# T08-Schematic.net
KiCad netlist of a schematic drawn in EAGLE
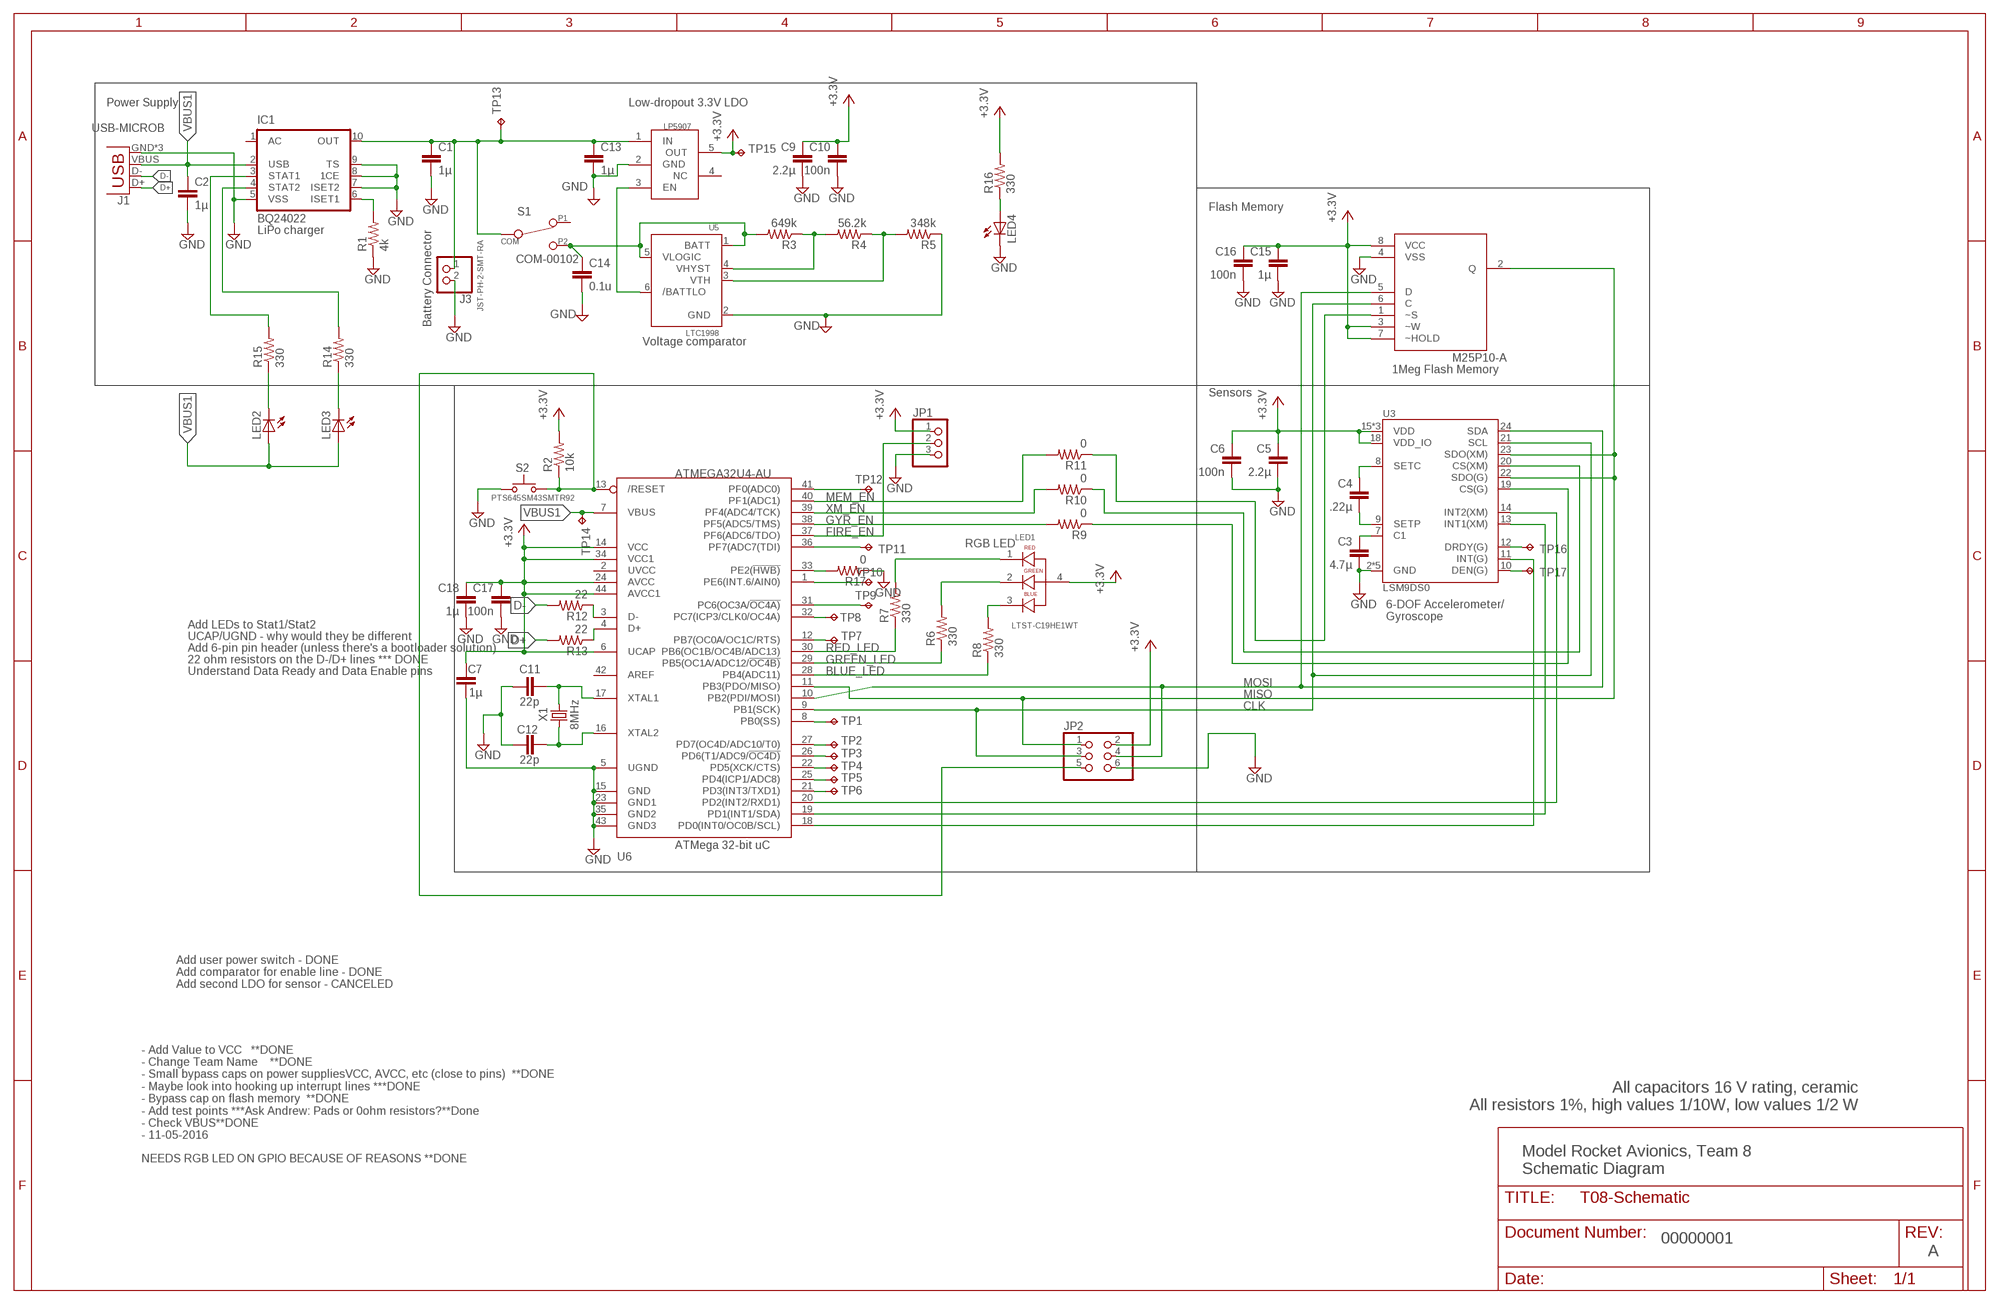
[diagram p0: schematic, sheet 1]

(export (version "E")
  (design (tool "Eeschema 10.0.6"))
  (components
    (comp (ref "C1")
      (value "1µ")
      (footprint "eagle-import:C0603")
      (libsource (lib "eagle-import") (part "C-EUC0603"))
    )
    (comp (ref "C2")
      (value "1µ")
      (footprint "eagle-import:C0805")
      (libsource (lib "eagle-import") (part "C-EUC0805"))
    )
    (comp (ref "C3")
      (value "4.7µ")
      (footprint "eagle-import:C0603")
      (libsource (lib "eagle-import") (part "C-EUC0603"))
    )
    (comp (ref "C4")
      (value ".22µ")
      (footprint "eagle-import:C0603")
      (libsource (lib "eagle-import") (part "C-EUC0603"))
    )
    (comp (ref "C5")
      (value "2.2µ")
      (footprint "eagle-import:C0603")
      (libsource (lib "eagle-import") (part "C-EUC0603"))
    )
    (comp (ref "C6")
      (value "100n")
      (footprint "eagle-import:C0603")
      (libsource (lib "eagle-import") (part "C-EUC0603"))
    )
    (comp (ref "C7")
      (value "1µ")
      (footprint "eagle-import:C0603")
      (libsource (lib "eagle-import") (part "C-EUC0603"))
    )
    (comp (ref "C9")
      (value "2.2µ")
      (footprint "eagle-import:C0603")
      (libsource (lib "eagle-import") (part "C-EUC0603"))
    )
    (comp (ref "C10")
      (value "100n")
      (footprint "eagle-import:C0603")
      (libsource (lib "eagle-import") (part "C-EUC0603"))
    )
    (comp (ref "C11")
      (value "22p")
      (footprint "eagle-import:C0603")
      (libsource (lib "eagle-import") (part "C-EUC0603"))
    )
    (comp (ref "C12")
      (value "22p")
      (footprint "eagle-import:C0603")
      (libsource (lib "eagle-import") (part "C-EUC0603"))
    )
    (comp (ref "C13")
      (value "1µ")
      (footprint "eagle-import:C0603")
      (libsource (lib "eagle-import") (part "C-EUC0603"))
    )
    (comp (ref "C14")
      (value "0.1u")
      (footprint "eagle-import:C0603")
      (libsource (lib "eagle-import") (part "C-EUC0603"))
    )
    (comp (ref "C15")
      (value "1µ")
      (footprint "eagle-import:C0603")
      (libsource (lib "eagle-import") (part "C-EUC0603"))
    )
    (comp (ref "C16")
      (value "100n")
      (footprint "eagle-import:C0603")
      (libsource (lib "eagle-import") (part "C-EUC0603"))
    )
    (comp (ref "C17")
      (value "100n")
      (footprint "eagle-import:C0603")
      (libsource (lib "eagle-import") (part "C-EUC0603"))
    )
    (comp (ref "C18")
      (value "1µ")
      (footprint "eagle-import:C0603")
      (libsource (lib "eagle-import") (part "C-EUC0603"))
    )
    (comp (ref "IC1")
      (value "BQ24022")
      (footprint "eagle-import:DRC-S-PVSON-N10")
      (libsource (lib "eagle-import") (part "BQ24022"))
    )
    (comp (ref "J1")
      (value "USB-MICROB")
      (footprint "eagle-import:USB-MICROB")
      (libsource (lib "eagle-import") (part "USB-MICROB"))
    )
    (comp (ref "J3")
      (value "JST-PH-2-SMT-RA")
      (footprint "eagle-import:JST-PH-2-SMT-RA")
      (libsource (lib "eagle-import") (part "JST_2PIN-SMT-RA"))
    )
    (comp (ref "JP1")
      (value "PINHD-1X3")
      (footprint "eagle-import:1X03")
      (libsource (lib "eagle-import") (part "PINHD-1X3"))
    )
    (comp (ref "JP2")
      (value "PINHD-2X3")
      (footprint "eagle-import:2X03")
      (libsource (lib "eagle-import") (part "PINHD-2X3"))
    )
    (comp (ref "LED1")
      (value "LTST-C19HE1WT")
      (footprint "eagle-import:LEDSC85P160X160X35-4N")
      (fields (field (name "MF") "Lite-On") (field (name "PRICE") "0.59 USD"))
      (libsource (lib "eagle-import") (part "LTST-C19HE1WT"))
    )
    (comp (ref "LED2")
      (value "LEDCHIP-LED0603")
      (footprint "eagle-import:CHIP-LED0603")
      (libsource (lib "eagle-import") (part "LEDCHIP-LED0603"))
    )
    (comp (ref "LED3")
      (value "LEDCHIP-LED0603")
      (footprint "eagle-import:CHIP-LED0603")
      (libsource (lib "eagle-import") (part "LEDCHIP-LED0603"))
    )
    (comp (ref "LED4")
      (value "LEDCHIP-LED0603")
      (footprint "eagle-import:CHIP-LED0603")
      (libsource (lib "eagle-import") (part "LEDCHIP-LED0603"))
    )
    (comp (ref "R1")
      (value "4k")
      (footprint "eagle-import:R0603")
      (libsource (lib "eagle-import") (part "R-US_R0603"))
    )
    (comp (ref "R2")
      (value "10k")
      (footprint "eagle-import:R0805")
      (libsource (lib "eagle-import") (part "R-US_R0805"))
    )
    (comp (ref "R3")
      (value "649k")
      (footprint "eagle-import:R0603")
      (libsource (lib "eagle-import") (part "R-US_R0603"))
    )
    (comp (ref "R4")
      (value "56.2k")
      (footprint "eagle-import:R0603")
      (libsource (lib "eagle-import") (part "R-US_R0603"))
    )
    (comp (ref "R5")
      (value "348k")
      (footprint "eagle-import:R0603")
      (libsource (lib "eagle-import") (part "R-US_R0603"))
    )
    (comp (ref "R6")
      (value "330")
      (footprint "eagle-import:R0805")
      (libsource (lib "eagle-import") (part "R-US_R0805"))
    )
    (comp (ref "R7")
      (value "330")
      (footprint "eagle-import:R0805")
      (libsource (lib "eagle-import") (part "R-US_R0805"))
    )
    (comp (ref "R8")
      (value "330")
      (footprint "eagle-import:R0805")
      (libsource (lib "eagle-import") (part "R-US_R0805"))
    )
    (comp (ref "R9")
      (value "0")
      (footprint "eagle-import:R0603")
      (libsource (lib "eagle-import") (part "R-US_R0603"))
    )
    (comp (ref "R10")
      (value "0")
      (footprint "eagle-import:R0603")
      (libsource (lib "eagle-import") (part "R-US_R0603"))
    )
    (comp (ref "R11")
      (value "0")
      (footprint "eagle-import:R0603")
      (libsource (lib "eagle-import") (part "R-US_R0603"))
    )
    (comp (ref "R12")
      (value "22")
      (footprint "eagle-import:R0603")
      (libsource (lib "eagle-import") (part "R-US_R0603"))
    )
    (comp (ref "R13")
      (value "22")
      (footprint "eagle-import:R0603")
      (libsource (lib "eagle-import") (part "R-US_R0603"))
    )
    (comp (ref "R14")
      (value "330")
      (footprint "eagle-import:R0805")
      (libsource (lib "eagle-import") (part "R-US_R0805"))
    )
    (comp (ref "R15")
      (value "330")
      (footprint "eagle-import:R0805")
      (libsource (lib "eagle-import") (part "R-US_R0805"))
    )
    (comp (ref "R16")
      (value "330")
      (footprint "eagle-import:R0805")
      (libsource (lib "eagle-import") (part "R-US_R0805"))
    )
    (comp (ref "R17")
      (value "0")
      (footprint "eagle-import:R0603")
      (libsource (lib "eagle-import") (part "R-US_R0603"))
    )
    (comp (ref "S1")
      (value "COM-00102")
      (footprint "eagle-import:ESWITCH")
      (libsource (lib "eagle-import") (part "COM-00102"))
    )
    (comp (ref "S2")
      (value "PTS645SM43SMTR92")
      (footprint "eagle-import:PTS645-SMD")
      (fields (field (name "MPN") "PTS645SM43SMTR92 LFS"))
      (libsource (lib "eagle-import") (part "PTS645S???SMTR"))
    )
    (comp (ref "TP1")
      (value "TPTP08R")
      (footprint "eagle-import:TP08R")
      (libsource (lib "eagle-import") (part "TPTP08R"))
    )
    (comp (ref "TP2")
      (value "TPTP08R")
      (footprint "eagle-import:TP08R")
      (libsource (lib "eagle-import") (part "TPTP08R"))
    )
    (comp (ref "TP3")
      (value "TPTP08R")
      (footprint "eagle-import:TP08R")
      (libsource (lib "eagle-import") (part "TPTP08R"))
    )
    (comp (ref "TP4")
      (value "TPTP08R")
      (footprint "eagle-import:TP08R")
      (libsource (lib "eagle-import") (part "TPTP08R"))
    )
    (comp (ref "TP5")
      (value "TPTP08R")
      (footprint "eagle-import:TP08R")
      (libsource (lib "eagle-import") (part "TPTP08R"))
    )
    (comp (ref "TP6")
      (value "TPTP08R")
      (footprint "eagle-import:TP08R")
      (libsource (lib "eagle-import") (part "TPTP08R"))
    )
    (comp (ref "TP7")
      (value "TPTP08R")
      (footprint "eagle-import:TP08R")
      (libsource (lib "eagle-import") (part "TPTP08R"))
    )
    (comp (ref "TP8")
      (value "TPTP08R")
      (footprint "eagle-import:TP08R")
      (libsource (lib "eagle-import") (part "TPTP08R"))
    )
    (comp (ref "TP9")
      (value "TPTP08R")
      (footprint "eagle-import:TP08R")
      (libsource (lib "eagle-import") (part "TPTP08R"))
    )
    (comp (ref "TP10")
      (value "TPTP08R")
      (footprint "eagle-import:TP08R")
      (libsource (lib "eagle-import") (part "TPTP08R"))
    )
    (comp (ref "TP11")
      (value "TPTP08R")
      (footprint "eagle-import:TP08R")
      (libsource (lib "eagle-import") (part "TPTP08R"))
    )
    (comp (ref "TP12")
      (value "TPTP08R")
      (footprint "eagle-import:TP08R")
      (libsource (lib "eagle-import") (part "TPTP08R"))
    )
    (comp (ref "TP13")
      (value "TPTP08R")
      (footprint "eagle-import:TP08R")
      (libsource (lib "eagle-import") (part "TPTP08R"))
    )
    (comp (ref "TP14")
      (value "TPTP08R")
      (footprint "eagle-import:TP08R")
      (libsource (lib "eagle-import") (part "TPTP08R"))
    )
    (comp (ref "TP15")
      (value "TPTP08R")
      (footprint "eagle-import:TP08R")
      (libsource (lib "eagle-import") (part "TPTP08R"))
    )
    (comp (ref "TP16")
      (value "TPTP08R")
      (footprint "eagle-import:TP08R")
      (libsource (lib "eagle-import") (part "TPTP08R"))
    )
    (comp (ref "TP17")
      (value "TPTP08R")
      (footprint "eagle-import:TP08R")
      (libsource (lib "eagle-import") (part "TPTP08R"))
    )
    (comp (ref "U1")
      (value "LP5907")
      (footprint "eagle-import:SOT23-5L")
      (libsource (lib "eagle-import") (part "LP5907"))
    )
    (comp (ref "U2")
      (value "M25P10-AVMN6TP_TR")
      (footprint "eagle-import:SOIC127P600X175-8N")
      (libsource (lib "eagle-import") (part "M25P10-AVMN6TP_TR"))
    )
    (comp (ref "U3")
      (value "LSM9DS0")
      (footprint "eagle-import:LGA-24")
      (fields (field (name "MF") "STMicroelectronics"))
      (libsource (lib "eagle-import") (part "LSM9DS0"))
    )
    (comp (ref "U5")
      (value "LTC1998")
      (footprint "eagle-import:TSOT23-6")
      (libsource (lib "eagle-import") (part "LTC1998"))
    )
    (comp (ref "U6")
      (value "ATMEGA32U4-AU")
      (footprint "eagle-import:TQFP44")
      (libsource (lib "eagle-import") (part "ATMEGA32U4-AU"))
    )
    (comp (ref "X1")
      (value "8MHz")
      (footprint "eagle-import:HC49")
      (fields (field (name "MPN") "ATS080B"))
      (libsource (lib "eagle-import") (part "CRYSTALS-NOGND-HC49/4H"))
    )
  )
  (nets
    (net (code "1") (name "+3.3V") (class "Default")
      (node (ref "C10") (pin "1") (pinfunction "1_1") (pintype "passive"))
      (node (ref "C15") (pin "1") (pinfunction "1_1") (pintype "passive"))
      (node (ref "C16") (pin "1") (pinfunction "1_1") (pintype "passive"))
      (node (ref "C17") (pin "1") (pinfunction "1_1") (pintype "passive"))
      (node (ref "C18") (pin "1") (pinfunction "1_1") (pintype "passive"))
      (node (ref "C5") (pin "1") (pinfunction "1_1") (pintype "passive"))
      (node (ref "C6") (pin "1") (pinfunction "1_1") (pintype "passive"))
      (node (ref "C7") (pin "1") (pinfunction "1_1") (pintype "passive"))
      (node (ref "C9") (pin "1") (pinfunction "1_1") (pintype "passive"))
      (node (ref "JP1") (pin "1") (pinfunction "1_1") (pintype "passive"))
      (node (ref "JP2") (pin "2") (pinfunction "2_2") (pintype "passive"))
      (node (ref "LED1") (pin "4") (pinfunction "4_4") (pintype "passive"))
      (node (ref "R16") (pin "2") (pinfunction "2_2") (pintype "passive"))
      (node (ref "R2") (pin "2") (pinfunction "2_2") (pintype "passive"))
      (node (ref "TP15") (pin "TP") (pinfunction "TP_TP") (pintype "input"))
      (node (ref "U1") (pin "5") (pinfunction "OUT_5") (pintype "bidirectional"))
      (node (ref "U2") (pin "3") (pinfunction "~{W}_3") (pintype "bidirectional"))
      (node (ref "U2") (pin "7") (pinfunction "~{HOLD}_7") (pintype "bidirectional"))
      (node (ref "U2") (pin "8") (pinfunction "VCC_8") (pintype "bidirectional"))
      (node (ref "U3") (pin "15") (pinfunction "VDD_15") (pintype "bidirectional"))
      (node (ref "U3") (pin "16") (pinfunction "VDD_16") (pintype "bidirectional"))
      (node (ref "U3") (pin "17") (pinfunction "VDD_17") (pintype "bidirectional"))
      (node (ref "U3") (pin "18") (pinfunction "VDD_IO_18") (pintype "bidirectional"))
      (node (ref "U6") (pin "14") (pinfunction "VCC_14") (pintype "bidirectional"))
      (node (ref "U6") (pin "24") (pinfunction "AVCC_24") (pintype "bidirectional"))
      (node (ref "U6") (pin "34") (pinfunction "VCC1_34") (pintype "bidirectional"))
      (node (ref "U6") (pin "44") (pinfunction "AVCC1_44") (pintype "bidirectional"))
      (node (ref "U6") (pin "6") (pinfunction "UCAP_6") (pintype "bidirectional"))
    )
    (net (code "2") (name "/BLUE_LED") (class "Default")
      (node (ref "R8") (pin "1") (pinfunction "1_1") (pintype "passive"))
      (node (ref "U6") (pin "28") (pinfunction "PB4(ADC11)_28") (pintype "bidirectional"))
    )
    (net (code "3") (name "/CLK") (class "Default")
      (node (ref "JP2") (pin "3") (pinfunction "3_3") (pintype "passive"))
      (node (ref "U2") (pin "6") (pinfunction "C_6") (pintype "bidirectional"))
      (node (ref "U3") (pin "21") (pinfunction "SCL_21") (pintype "bidirectional"))
      (node (ref "U6") (pin "9") (pinfunction "PB1(SCK)_9") (pintype "bidirectional"))
    )
    (net (code "4") (name "/FIRE_EN") (class "Default")
      (node (ref "JP1") (pin "2") (pinfunction "2_2") (pintype "passive"))
      (node (ref "U6") (pin "37") (pinfunction "PF6(ADC6/TDO)_37") (pintype "bidirectional"))
    )
    (net (code "5") (name "/GREEN_LED") (class "Default")
      (node (ref "R6") (pin "1") (pinfunction "1_1") (pintype "passive"))
      (node (ref "U6") (pin "29") (pinfunction "PB5(OC1A/ADC12/~{OC4B})_29") (pintype "bidirectional"))
    )
    (net (code "6") (name "/GYR_EN") (class "Default")
      (node (ref "R9") (pin "1") (pinfunction "1_1") (pintype "passive"))
      (node (ref "U3") (pin "19") (pinfunction "CS(G)_19") (pintype "bidirectional"))
    )
    (net (code "7") (name "/MEM_EN") (class "Default")
      (node (ref "R11") (pin "1") (pinfunction "1_1") (pintype "passive"))
      (node (ref "U2") (pin "1") (pinfunction "~{S}_1") (pintype "bidirectional"))
    )
    (net (code "8") (name "/MISO") (class "Default")
      (node (ref "JP2") (pin "1") (pinfunction "1_1") (pintype "passive"))
      (node (ref "U2") (pin "2") (pinfunction "Q_2") (pintype "bidirectional"))
      (node (ref "U3") (pin "22") (pinfunction "SDO(G)_22") (pintype "bidirectional"))
      (node (ref "U3") (pin "23") (pinfunction "SDO(XM)_23") (pintype "bidirectional"))
      (node (ref "U6") (pin "11") (pinfunction "PB3(PDO/MISO)_11") (pintype "bidirectional"))
    )
    (net (code "9") (name "/MOSI") (class "Default")
      (node (ref "JP2") (pin "4") (pinfunction "4_4") (pintype "passive"))
      (node (ref "U2") (pin "5") (pinfunction "D_5") (pintype "bidirectional"))
      (node (ref "U3") (pin "24") (pinfunction "SDA_24") (pintype "bidirectional"))
      (node (ref "U6") (pin "10") (pinfunction "PB2(PDI/MOSI)_10") (pintype "bidirectional"))
    )
    (net (code "10") (name "/RED_LED") (class "Default")
      (node (ref "R7") (pin "1") (pinfunction "1_1") (pintype "passive"))
      (node (ref "U6") (pin "30") (pinfunction "PB6(OC1B/OC4B/ADC13)_30") (pintype "bidirectional"))
    )
    (net (code "11") (name "/XM_EN") (class "Default")
      (node (ref "R10") (pin "1") (pinfunction "1_1") (pintype "passive"))
      (node (ref "U3") (pin "20") (pinfunction "CS(XM)_20") (pintype "bidirectional"))
    )
    (net (code "12") (name "D+") (class "Default")
      (node (ref "J1") (pin "D+") (pinfunction "D+_D+") (pintype "bidirectional"))
      (node (ref "R13") (pin "2") (pinfunction "2_2") (pintype "passive"))
    )
    (net (code "13") (name "D-") (class "Default")
      (node (ref "J1") (pin "D-") (pinfunction "D-_D-") (pintype "bidirectional"))
      (node (ref "R12") (pin "2") (pinfunction "2_2") (pintype "passive"))
    )
    (net (code "14") (name "GND") (class "Default")
      (node (ref "C1") (pin "2") (pinfunction "2_2") (pintype "passive"))
      (node (ref "C10") (pin "2") (pinfunction "2_2") (pintype "passive"))
      (node (ref "C11") (pin "2") (pinfunction "2_2") (pintype "passive"))
      (node (ref "C12") (pin "2") (pinfunction "2_2") (pintype "passive"))
      (node (ref "C13") (pin "2") (pinfunction "2_2") (pintype "passive"))
      (node (ref "C14") (pin "2") (pinfunction "2_2") (pintype "passive"))
      (node (ref "C15") (pin "2") (pinfunction "2_2") (pintype "passive"))
      (node (ref "C16") (pin "2") (pinfunction "2_2") (pintype "passive"))
      (node (ref "C17") (pin "2") (pinfunction "2_2") (pintype "passive"))
      (node (ref "C18") (pin "2") (pinfunction "2_2") (pintype "passive"))
      (node (ref "C2") (pin "2") (pinfunction "2_2") (pintype "passive"))
      (node (ref "C3") (pin "1") (pinfunction "1_1") (pintype "passive"))
      (node (ref "C5") (pin "2") (pinfunction "2_2") (pintype "passive"))
      (node (ref "C6") (pin "2") (pinfunction "2_2") (pintype "passive"))
      (node (ref "C7") (pin "2") (pinfunction "2_2") (pintype "passive"))
      (node (ref "C9") (pin "2") (pinfunction "2_2") (pintype "passive"))
      (node (ref "IC1") (pin "5") (pinfunction "VSS_5") (pintype "power_in"))
      (node (ref "IC1") (pin "7") (pinfunction "ISET2_7") (pintype "input"))
      (node (ref "IC1") (pin "8") (pinfunction "1CE_8") (pintype "input"))
      (node (ref "IC1") (pin "9") (pinfunction "TS_9") (pintype "input"))
      (node (ref "J1") (pin "GND") (pinfunction "GND_GND") (pintype "bidirectional"))
      (node (ref "J1") (pin "MT1") (pinfunction "GND_MT1") (pintype "bidirectional"))
      (node (ref "J1") (pin "MT2") (pinfunction "GND_MT2") (pintype "bidirectional"))
      (node (ref "J3") (pin "2") (pinfunction "1_2") (pintype "passive"))
      (node (ref "JP1") (pin "3") (pinfunction "3_3") (pintype "passive"))
      (node (ref "JP2") (pin "6") (pinfunction "6_6") (pintype "passive"))
      (node (ref "LED4") (pin "C") (pinfunction "C_C") (pintype "passive"))
      (node (ref "R1") (pin "1") (pinfunction "1_1") (pintype "passive"))
      (node (ref "R17") (pin "1") (pinfunction "1_1") (pintype "passive"))
      (node (ref "R5") (pin "1") (pinfunction "1_1") (pintype "passive"))
      (node (ref "S2") (pin "1") (pinfunction "P_1") (pintype "passive"))
      (node (ref "S2") (pin "2") (pinfunction "P_2") (pintype "passive"))
      (node (ref "U1") (pin "2") (pinfunction "GND_2") (pintype "bidirectional"))
      (node (ref "U2") (pin "4") (pinfunction "VSS_4") (pintype "bidirectional"))
      (node (ref "U3") (pin "2") (pinfunction "GND_2") (pintype "bidirectional"))
      (node (ref "U3") (pin "3") (pinfunction "GND_3") (pintype "bidirectional"))
      (node (ref "U3") (pin "4") (pinfunction "GND_4") (pintype "bidirectional"))
      (node (ref "U3") (pin "5") (pinfunction "GND_5") (pintype "bidirectional"))
      (node (ref "U3") (pin "6") (pinfunction "GND_6") (pintype "bidirectional"))
      (node (ref "U5") (pin "2") (pinfunction "GND_2") (pintype "bidirectional"))
      (node (ref "U6") (pin "15") (pinfunction "GND_15") (pintype "bidirectional"))
      (node (ref "U6") (pin "23") (pinfunction "GND1_23") (pintype "bidirectional"))
      (node (ref "U6") (pin "35") (pinfunction "GND2_35") (pintype "bidirectional"))
      (node (ref "U6") (pin "43") (pinfunction "GND3_43") (pintype "bidirectional"))
      (node (ref "U6") (pin "5") (pinfunction "UGND_5") (pintype "bidirectional"))
    )
    (net (code "15") (name "Net-(IC1A-ISET1)") (class "Default")
      (node (ref "IC1") (pin "6") (pinfunction "ISET1_6") (pintype "input"))
      (node (ref "R1") (pin "2") (pinfunction "2_2") (pintype "passive"))
    )
    (net (code "16") (name "Net-(IC1A-OUT)") (class "Default")
      (node (ref "C1") (pin "1") (pinfunction "1_1") (pintype "passive"))
      (node (ref "C13") (pin "1") (pinfunction "1_1") (pintype "passive"))
      (node (ref "IC1") (pin "10") (pinfunction "OUT_10") (pintype "output"))
      (node (ref "J3") (pin "1") (pinfunction "2_1") (pintype "passive"))
      (node (ref "S1") (pin "2") (pinfunction "COM_2") (pintype "bidirectional"))
      (node (ref "TP13") (pin "TP") (pinfunction "TP_TP") (pintype "input"))
      (node (ref "U1") (pin "1") (pinfunction "IN_1") (pintype "bidirectional"))
    )
    (net (code "17") (name "Net-(IC1A-STAT1)") (class "Default")
      (node (ref "IC1") (pin "3") (pinfunction "STAT1_3") (pintype "bidirectional"))
      (node (ref "R15") (pin "2") (pinfunction "2_2") (pintype "passive"))
    )
    (net (code "18") (name "Net-(IC1A-STAT2)") (class "Default")
      (node (ref "IC1") (pin "4") (pinfunction "STAT2_4") (pintype "bidirectional"))
      (node (ref "R14") (pin "2") (pinfunction "2_2") (pintype "passive"))
    )
    (net (code "19") (name "Net-(LED1-Pad1)") (class "Default")
      (node (ref "LED1") (pin "1") (pinfunction "1_1") (pintype "passive"))
      (node (ref "R7") (pin "2") (pinfunction "2_2") (pintype "passive"))
    )
    (net (code "20") (name "Net-(LED1-Pad2)") (class "Default")
      (node (ref "LED1") (pin "2") (pinfunction "2_2") (pintype "passive"))
      (node (ref "R6") (pin "2") (pinfunction "2_2") (pintype "passive"))
    )
    (net (code "21") (name "Net-(LED1-Pad3)") (class "Default")
      (node (ref "LED1") (pin "3") (pinfunction "3_3") (pintype "passive"))
      (node (ref "R8") (pin "2") (pinfunction "2_2") (pintype "passive"))
    )
    (net (code "22") (name "Net-(LED2-PadC)") (class "Default")
      (node (ref "LED2") (pin "C") (pinfunction "C_C") (pintype "passive"))
      (node (ref "R15") (pin "1") (pinfunction "1_1") (pintype "passive"))
    )
    (net (code "23") (name "Net-(LED3-PadC)") (class "Default")
      (node (ref "LED3") (pin "C") (pinfunction "C_C") (pintype "passive"))
      (node (ref "R14") (pin "1") (pinfunction "1_1") (pintype "passive"))
    )
    (net (code "24") (name "Net-(LED4-PadA)") (class "Default")
      (node (ref "LED4") (pin "A") (pinfunction "A_A") (pintype "passive"))
      (node (ref "R16") (pin "1") (pinfunction "1_1") (pintype "passive"))
    )
    (net (code "25") (name "Net-(S1-P2)") (class "Default")
      (node (ref "C14") (pin "1") (pinfunction "1_1") (pintype "passive"))
      (node (ref "R3") (pin "2") (pinfunction "2_2") (pintype "passive"))
      (node (ref "S1") (pin "3") (pinfunction "P2_3") (pintype "bidirectional"))
      (node (ref "U5") (pin "1") (pinfunction "BATT_1") (pintype "bidirectional"))
      (node (ref "U5") (pin "5") (pinfunction "VLOGIC_5") (pintype "bidirectional"))
    )
    (net (code "26") (name "Net-(U1-EN)") (class "Default")
      (node (ref "U1") (pin "3") (pinfunction "EN_3") (pintype "bidirectional"))
      (node (ref "U5") (pin "6") (pinfunction "/BATTLO_6") (pintype "bidirectional"))
    )
    (net (code "27") (name "Net-(U3-C1)") (class "Default")
      (node (ref "C3") (pin "2") (pinfunction "2_2") (pintype "passive"))
      (node (ref "U3") (pin "7") (pinfunction "C1_7") (pintype "bidirectional"))
    )
    (net (code "28") (name "Net-(U3-DEN(G))") (class "Default")
      (node (ref "TP17") (pin "TP") (pinfunction "TP_TP") (pintype "input"))
      (node (ref "U3") (pin "10") (pinfunction "DEN(G)_10") (pintype "bidirectional"))
    )
    (net (code "29") (name "Net-(U3-DRDY(G))") (class "Default")
      (node (ref "TP16") (pin "TP") (pinfunction "TP_TP") (pintype "input"))
      (node (ref "U3") (pin "12") (pinfunction "DRDY(G)_12") (pintype "bidirectional"))
    )
    (net (code "30") (name "Net-(U3-INT(G))") (class "Default")
      (node (ref "U3") (pin "11") (pinfunction "INT(G)_11") (pintype "bidirectional"))
      (node (ref "U6") (pin "18") (pinfunction "PD0(INT0/OC0B/SCL)_18") (pintype "bidirectional"))
    )
    (net (code "31") (name "Net-(U3-INT1(XM))") (class "Default")
      (node (ref "U3") (pin "13") (pinfunction "INT1(XM)_13") (pintype "bidirectional"))
      (node (ref "U6") (pin "19") (pinfunction "PD1(INT1/SDA)_19") (pintype "bidirectional"))
    )
    (net (code "32") (name "Net-(U3-INT2(XM))") (class "Default")
      (node (ref "U3") (pin "14") (pinfunction "INT2(XM)_14") (pintype "bidirectional"))
      (node (ref "U6") (pin "20") (pinfunction "PD2(INT2/RXD1)_20") (pintype "bidirectional"))
    )
    (net (code "33") (name "Net-(U3-SETC)") (class "Default")
      (node (ref "C4") (pin "2") (pinfunction "2_2") (pintype "passive"))
      (node (ref "U3") (pin "8") (pinfunction "SETC_8") (pintype "bidirectional"))
    )
    (net (code "34") (name "Net-(U3-SETP)") (class "Default")
      (node (ref "C4") (pin "1") (pinfunction "1_1") (pintype "passive"))
      (node (ref "U3") (pin "9") (pinfunction "SETP_9") (pintype "bidirectional"))
    )
    (net (code "35") (name "Net-(U5-VHYST)") (class "Default")
      (node (ref "R3") (pin "1") (pinfunction "1_1") (pintype "passive"))
      (node (ref "R4") (pin "2") (pinfunction "2_2") (pintype "passive"))
      (node (ref "U5") (pin "4") (pinfunction "VHYST_4") (pintype "bidirectional"))
    )
    (net (code "36") (name "Net-(U5-VTH)") (class "Default")
      (node (ref "R4") (pin "1") (pinfunction "1_1") (pintype "passive"))
      (node (ref "R5") (pin "2") (pinfunction "2_2") (pintype "passive"))
      (node (ref "U5") (pin "3") (pinfunction "VTH_3") (pintype "bidirectional"))
    )
    (net (code "37") (name "Net-(U6-D+)") (class "Default")
      (node (ref "R13") (pin "1") (pinfunction "1_1") (pintype "passive"))
      (node (ref "U6") (pin "4") (pinfunction "D+_4") (pintype "bidirectional"))
    )
    (net (code "38") (name "Net-(U6-D-)") (class "Default")
      (node (ref "R12") (pin "1") (pinfunction "1_1") (pintype "passive"))
      (node (ref "U6") (pin "3") (pinfunction "D-_3") (pintype "bidirectional"))
    )
    (net (code "39") (name "Net-(U6-PB0(SS))") (class "Default")
      (node (ref "TP1") (pin "TP") (pinfunction "TP_TP") (pintype "input"))
      (node (ref "U6") (pin "8") (pinfunction "PB0(SS)_8") (pintype "bidirectional"))
    )
    (net (code "40") (name "Net-(U6-PB7(OC0A{slash}OC1C{slash}RTS))") (class "Default")
      (node (ref "TP7") (pin "TP") (pinfunction "TP_TP") (pintype "input"))
      (node (ref "U6") (pin "12") (pinfunction "PB7(OC0A/OC1C/RTS)_12") (pintype "bidirectional"))
    )
    (net (code "41") (name "Net-(U6-PC6(OC3A{slash}~{OC4A}))") (class "Default")
      (node (ref "TP9") (pin "TP") (pinfunction "TP_TP") (pintype "input"))
      (node (ref "U6") (pin "31") (pinfunction "PC6(OC3A/~{OC4A})_31") (pintype "bidirectional"))
    )
    (net (code "42") (name "Net-(U6-PC7(ICP3{slash}CLK0{slash}OC4A))") (class "Default")
      (node (ref "TP8") (pin "TP") (pinfunction "TP_TP") (pintype "input"))
      (node (ref "U6") (pin "32") (pinfunction "PC7(ICP3/CLK0/OC4A)_32") (pintype "bidirectional"))
    )
    (net (code "43") (name "Net-(U6-PD3(INT3{slash}TXD1))") (class "Default")
      (node (ref "TP6") (pin "TP") (pinfunction "TP_TP") (pintype "input"))
      (node (ref "U6") (pin "21") (pinfunction "PD3(INT3/TXD1)_21") (pintype "bidirectional"))
    )
    (net (code "44") (name "Net-(U6-PD4(ICP1{slash}ADC8))") (class "Default")
      (node (ref "TP5") (pin "TP") (pinfunction "TP_TP") (pintype "input"))
      (node (ref "U6") (pin "25") (pinfunction "PD4(ICP1/ADC8)_25") (pintype "bidirectional"))
    )
    (net (code "45") (name "Net-(U6-PD5(XCK{slash}CTS))") (class "Default")
      (node (ref "TP4") (pin "TP") (pinfunction "TP_TP") (pintype "input"))
      (node (ref "U6") (pin "22") (pinfunction "PD5(XCK/CTS)_22") (pintype "bidirectional"))
    )
    (net (code "46") (name "Net-(U6-PD6(T1{slash}ADC9{slash}~{OC4D}))") (class "Default")
      (node (ref "TP3") (pin "TP") (pinfunction "TP_TP") (pintype "input"))
      (node (ref "U6") (pin "26") (pinfunction "PD6(T1/ADC9/~{OC4D})_26") (pintype "bidirectional"))
    )
    (net (code "47") (name "Net-(U6-PD7(OC4D{slash}ADC10{slash}T0))") (class "Default")
      (node (ref "TP2") (pin "TP") (pinfunction "TP_TP") (pintype "input"))
      (node (ref "U6") (pin "27") (pinfunction "PD7(OC4D/ADC10/T0)_27") (pintype "bidirectional"))
    )
    (net (code "48") (name "Net-(U6-PE2(~{HWB}))") (class "Default")
      (node (ref "R17") (pin "2") (pinfunction "2_2") (pintype "passive"))
      (node (ref "U6") (pin "33") (pinfunction "PE2(~{HWB})_33") (pintype "bidirectional"))
    )
    (net (code "49") (name "Net-(U6-PE6(INT.6{slash}AIN0))") (class "Default")
      (node (ref "TP10") (pin "TP") (pinfunction "TP_TP") (pintype "input"))
      (node (ref "U6") (pin "1") (pinfunction "PE6(INT.6/AIN0)_1") (pintype "bidirectional"))
    )
    (net (code "50") (name "Net-(U6-PF0(ADC0))") (class "Default")
      (node (ref "TP12") (pin "TP") (pinfunction "TP_TP") (pintype "input"))
      (node (ref "U6") (pin "41") (pinfunction "PF0(ADC0)_41") (pintype "bidirectional"))
    )
    (net (code "51") (name "Net-(U6-PF1(ADC1))") (class "Default")
      (node (ref "R11") (pin "2") (pinfunction "2_2") (pintype "passive"))
      (node (ref "U6") (pin "40") (pinfunction "PF1(ADC1)_40") (pintype "bidirectional"))
    )
    (net (code "52") (name "Net-(U6-PF4(ADC4{slash}TCK))") (class "Default")
      (node (ref "R10") (pin "2") (pinfunction "2_2") (pintype "passive"))
      (node (ref "U6") (pin "39") (pinfunction "PF4(ADC4/TCK)_39") (pintype "bidirectional"))
    )
    (net (code "53") (name "Net-(U6-PF5(ADC5{slash}TMS))") (class "Default")
      (node (ref "R9") (pin "2") (pinfunction "2_2") (pintype "passive"))
      (node (ref "U6") (pin "38") (pinfunction "PF5(ADC5/TMS)_38") (pintype "bidirectional"))
    )
    (net (code "54") (name "Net-(U6-PF7(ADC7(TDI))") (class "Default")
      (node (ref "TP11") (pin "TP") (pinfunction "TP_TP") (pintype "input"))
      (node (ref "U6") (pin "36") (pinfunction "PF7(ADC7(TDI)_36") (pintype "bidirectional"))
    )
    (net (code "55") (name "Net-(U6-XTAL1)") (class "Default")
      (node (ref "C11") (pin "1") (pinfunction "1_1") (pintype "passive"))
      (node (ref "U6") (pin "17") (pinfunction "XTAL1_17") (pintype "bidirectional"))
      (node (ref "X1") (pin "1") (pinfunction "1_1") (pintype "passive"))
    )
    (net (code "56") (name "Net-(U6-XTAL2)") (class "Default")
      (node (ref "C12") (pin "1") (pinfunction "1_1") (pintype "passive"))
      (node (ref "U6") (pin "16") (pinfunction "XTAL2_16") (pintype "bidirectional"))
      (node (ref "X1") (pin "2") (pinfunction "2_2") (pintype "passive"))
    )
    (net (code "57") (name "Net-(U6-{slash}RESET)") (class "Default")
      (node (ref "JP2") (pin "5") (pinfunction "5_5") (pintype "passive"))
      (node (ref "R2") (pin "1") (pinfunction "1_1") (pintype "passive"))
      (node (ref "S2") (pin "3") (pinfunction "S_3") (pintype "passive"))
      (node (ref "S2") (pin "4") (pinfunction "S_4") (pintype "passive"))
      (node (ref "U6") (pin "13") (pinfunction "/RESET_13") (pintype "bidirectional"))
    )
    (net (code "58") (name "VBUS1") (class "Default")
      (node (ref "C2") (pin "1") (pinfunction "1_1") (pintype "passive"))
      (node (ref "IC1") (pin "2") (pinfunction "USB_2") (pintype "bidirectional"))
      (node (ref "J1") (pin "VBUS") (pinfunction "VBUS_VBUS") (pintype "bidirectional"))
      (node (ref "LED2") (pin "A") (pinfunction "A_A") (pintype "passive"))
      (node (ref "LED3") (pin "A") (pinfunction "A_A") (pintype "passive"))
      (node (ref "TP14") (pin "TP") (pinfunction "TP_TP") (pintype "input"))
      (node (ref "U6") (pin "7") (pinfunction "VBUS_7") (pintype "bidirectional"))
    )
    (net (code "59") (name "unconnected-(IC1A-AC-Pad1)") (class "Default")
      (node (ref "IC1") (pin "1") (pinfunction "AC_1") (pintype "input"))
    )
    (net (code "60") (name "unconnected-(S1-P1-Pad1)") (class "Default")
      (node (ref "S1") (pin "1") (pinfunction "P1_1") (pintype "bidirectional"))
    )
    (net (code "61") (name "unconnected-(U1-NC-Pad4)") (class "Default")
      (node (ref "U1") (pin "4") (pinfunction "NC_4") (pintype "bidirectional"))
    )
    (net (code "62") (name "unconnected-(U6-AREF-Pad42)") (class "Default")
      (node (ref "U6") (pin "42") (pinfunction "AREF_42") (pintype "bidirectional"))
    )
    (net (code "63") (name "unconnected-(U6-UVCC-Pad2)") (class "Default")
      (node (ref "U6") (pin "2") (pinfunction "UVCC_2") (pintype "bidirectional"))
    )
  )
)
